# Pixie328.net
KiCad netlist of a schematic drawn in EAGLE
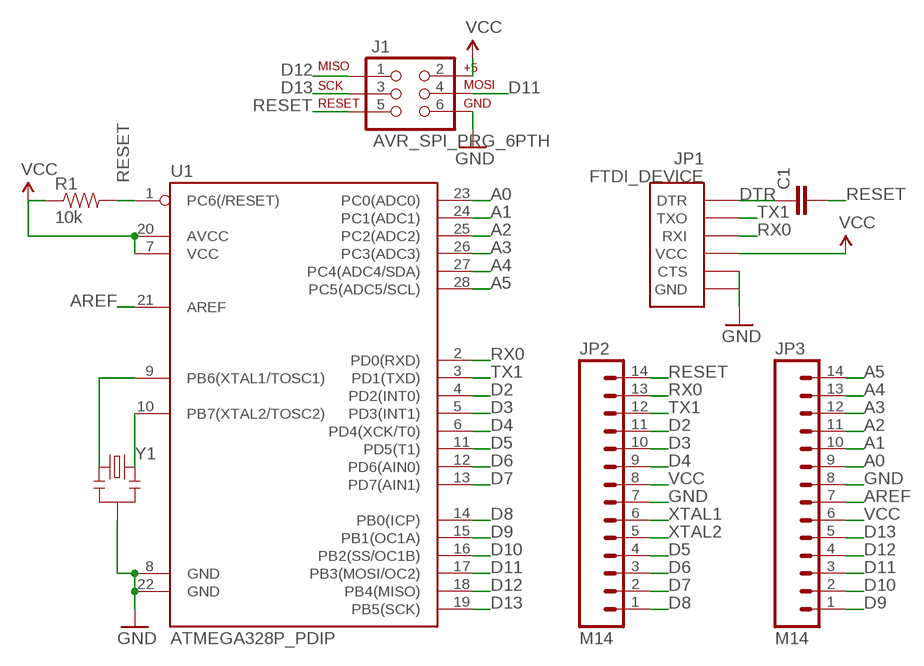
[diagram p0: schematic, sheet 1]

(export (version "E")
  (design (tool "Eeschema 10.0.6"))
  (components
    (comp (ref "C1")
      (value "CAPEZ")
      (footprint "eagle-import:CAP-PTH-SMALLEZ")
      (libsource (lib "eagle-import") (part "CAPEZ"))
    )
    (comp (ref "J1")
      (value "AVR_SPI_PRG_6PTH")
      (footprint "eagle-import:2X3")
      (libsource (lib "eagle-import") (part "AVR_SPI_PRG_6PTH"))
    )
    (comp (ref "JP1")
      (value "FTDI_DEVICE")
      (footprint "eagle-import:FTDI_DEVICE_SIDE")
      (libsource (lib "eagle-import") (part "FTDI_DEVICE"))
    )
    (comp (ref "JP2")
      (value "M14")
      (footprint "eagle-import:1X14")
      (libsource (lib "eagle-import") (part "M14"))
    )
    (comp (ref "JP3")
      (value "M14")
      (footprint "eagle-import:1X14")
      (libsource (lib "eagle-import") (part "M14"))
    )
    (comp (ref "R1")
      (value "10k")
      (footprint "eagle-import:AXIAL-0.3")
      (libsource (lib "eagle-import") (part "RESISTORAXIAL-0.3"))
    )
    (comp (ref "U1")
      (value "ATMEGA328P_PDIP")
      (footprint "eagle-import:DIL28-3")
      (libsource (lib "eagle-import") (part "ATMEGA328P_PDIP"))
    )
    (comp (ref "Y1")
      (value "RESONATORPTH")
      (footprint "eagle-import:RESONATOR-PTH")
      (libsource (lib "eagle-import") (part "RESONATORPTH"))
    )
  )
  (nets
    (net (code "1") (name "/A0") (class "Default")
      (node (ref "JP3") (pin "9") (pinfunction "9_9") (pintype "passive"))
      (node (ref "U1") (pin "23") (pinfunction "PC0(ADC0)_23") (pintype "bidirectional"))
    )
    (net (code "2") (name "/A1") (class "Default")
      (node (ref "JP3") (pin "10") (pinfunction "10_10") (pintype "passive"))
      (node (ref "U1") (pin "24") (pinfunction "PC1(ADC1)_24") (pintype "bidirectional"))
    )
    (net (code "3") (name "/A2") (class "Default")
      (node (ref "JP3") (pin "11") (pinfunction "11_11") (pintype "passive"))
      (node (ref "U1") (pin "25") (pinfunction "PC2(ADC2)_25") (pintype "bidirectional"))
    )
    (net (code "4") (name "/A3") (class "Default")
      (node (ref "JP3") (pin "12") (pinfunction "12_12") (pintype "passive"))
      (node (ref "U1") (pin "26") (pinfunction "PC3(ADC3)_26") (pintype "bidirectional"))
    )
    (net (code "5") (name "/A4") (class "Default")
      (node (ref "JP3") (pin "13") (pinfunction "13_13") (pintype "passive"))
      (node (ref "U1") (pin "27") (pinfunction "PC4(ADC4/SDA)_27") (pintype "bidirectional"))
    )
    (net (code "6") (name "/A5") (class "Default")
      (node (ref "JP3") (pin "14") (pinfunction "14_14") (pintype "passive"))
      (node (ref "U1") (pin "28") (pinfunction "PC5(ADC5/SCL)_28") (pintype "bidirectional"))
    )
    (net (code "7") (name "/AREF") (class "Default")
      (node (ref "JP3") (pin "7") (pinfunction "7_7") (pintype "passive"))
      (node (ref "U1") (pin "21") (pinfunction "AREF_21") (pintype "bidirectional"))
    )
    (net (code "8") (name "/D2") (class "Default")
      (node (ref "JP2") (pin "11") (pinfunction "11_11") (pintype "passive"))
      (node (ref "U1") (pin "4") (pinfunction "PD2(INT0)_4") (pintype "bidirectional"))
    )
    (net (code "9") (name "/D3") (class "Default")
      (node (ref "JP2") (pin "10") (pinfunction "10_10") (pintype "passive"))
      (node (ref "U1") (pin "5") (pinfunction "PD3(INT1)_5") (pintype "bidirectional"))
    )
    (net (code "10") (name "/D4") (class "Default")
      (node (ref "JP2") (pin "9") (pinfunction "9_9") (pintype "passive"))
      (node (ref "U1") (pin "6") (pinfunction "PD4(XCK/T0)_6") (pintype "bidirectional"))
    )
    (net (code "11") (name "/D5") (class "Default")
      (node (ref "JP2") (pin "4") (pinfunction "4_4") (pintype "passive"))
      (node (ref "U1") (pin "11") (pinfunction "PD5(T1)_11") (pintype "bidirectional"))
    )
    (net (code "12") (name "/D6") (class "Default")
      (node (ref "JP2") (pin "3") (pinfunction "3_3") (pintype "passive"))
      (node (ref "U1") (pin "12") (pinfunction "PD6(AIN0)_12") (pintype "bidirectional"))
    )
    (net (code "13") (name "/D7") (class "Default")
      (node (ref "JP2") (pin "2") (pinfunction "2_2") (pintype "passive"))
      (node (ref "U1") (pin "13") (pinfunction "PD7(AIN1)_13") (pintype "bidirectional"))
    )
    (net (code "14") (name "/D8") (class "Default")
      (node (ref "JP2") (pin "1") (pinfunction "1_1") (pintype "passive"))
      (node (ref "U1") (pin "14") (pinfunction "PB0(ICP)_14") (pintype "bidirectional"))
    )
    (net (code "15") (name "/D9") (class "Default")
      (node (ref "JP3") (pin "1") (pinfunction "1_1") (pintype "passive"))
      (node (ref "U1") (pin "15") (pinfunction "PB1(OC1A)_15") (pintype "bidirectional"))
    )
    (net (code "16") (name "/D10") (class "Default")
      (node (ref "JP3") (pin "2") (pinfunction "2_2") (pintype "passive"))
      (node (ref "U1") (pin "16") (pinfunction "PB2(SS/OC1B)_16") (pintype "bidirectional"))
    )
    (net (code "17") (name "/D11") (class "Default")
      (node (ref "J1") (pin "4") (pinfunction "4_4") (pintype "passive"))
      (node (ref "JP3") (pin "3") (pinfunction "3_3") (pintype "passive"))
      (node (ref "U1") (pin "17") (pinfunction "PB3(MOSI/OC2)_17") (pintype "bidirectional"))
    )
    (net (code "18") (name "/D12") (class "Default")
      (node (ref "J1") (pin "1") (pinfunction "1_1") (pintype "passive"))
      (node (ref "JP3") (pin "4") (pinfunction "4_4") (pintype "passive"))
      (node (ref "U1") (pin "18") (pinfunction "PB4(MISO)_18") (pintype "bidirectional"))
    )
    (net (code "19") (name "/D13") (class "Default")
      (node (ref "J1") (pin "3") (pinfunction "3_3") (pintype "passive"))
      (node (ref "JP3") (pin "5") (pinfunction "5_5") (pintype "passive"))
      (node (ref "U1") (pin "19") (pinfunction "PB5(SCK)_19") (pintype "bidirectional"))
    )
    (net (code "20") (name "/DTR") (class "Default")
      (node (ref "C1") (pin "1") (pinfunction "1_1") (pintype "passive"))
      (node (ref "JP1") (pin "P$1") (pinfunction "DTR_P$1") (pintype "bidirectional"))
    )
    (net (code "21") (name "/RESET") (class "Default")
      (node (ref "C1") (pin "2") (pinfunction "2_2") (pintype "passive"))
      (node (ref "J1") (pin "5") (pinfunction "5_5") (pintype "passive"))
      (node (ref "JP2") (pin "14") (pinfunction "14_14") (pintype "passive"))
      (node (ref "R1") (pin "P$2") (pinfunction "2_P$2") (pintype "passive"))
      (node (ref "U1") (pin "1") (pinfunction "PC6(/RESET)_1") (pintype "bidirectional"))
    )
    (net (code "22") (name "/RX0") (class "Default")
      (node (ref "JP1") (pin "P$3") (pinfunction "RXI_P$3") (pintype "bidirectional"))
      (node (ref "JP2") (pin "13") (pinfunction "13_13") (pintype "passive"))
      (node (ref "U1") (pin "2") (pinfunction "PD0(RXD)_2") (pintype "bidirectional"))
    )
    (net (code "23") (name "/TX1") (class "Default")
      (node (ref "JP1") (pin "P$2") (pinfunction "TXO_P$2") (pintype "bidirectional"))
      (node (ref "JP2") (pin "12") (pinfunction "12_12") (pintype "passive"))
      (node (ref "U1") (pin "3") (pinfunction "PD1(TXD)_3") (pintype "bidirectional"))
    )
    (net (code "24") (name "/XTAL1") (class "Default")
      (node (ref "JP2") (pin "6") (pinfunction "6_6") (pintype "passive"))
      (node (ref "U1") (pin "9") (pinfunction "PB6(XTAL1/TOSC1)_9") (pintype "bidirectional"))
      (node (ref "Y1") (pin "1") (pinfunction "1_1") (pintype "passive"))
    )
    (net (code "25") (name "/XTAL2") (class "Default")
      (node (ref "JP2") (pin "5") (pinfunction "5_5") (pintype "passive"))
      (node (ref "U1") (pin "10") (pinfunction "PB7(XTAL2/TOSC2)_10") (pintype "bidirectional"))
      (node (ref "Y1") (pin "3") (pinfunction "3_3") (pintype "passive"))
    )
    (net (code "26") (name "GND") (class "Default")
      (node (ref "J1") (pin "6") (pinfunction "6_6") (pintype "passive"))
      (node (ref "JP1") (pin "P$5") (pinfunction "CTS_P$5") (pintype "bidirectional"))
      (node (ref "JP1") (pin "P$6") (pinfunction "GND_P$6") (pintype "bidirectional"))
      (node (ref "JP2") (pin "7") (pinfunction "7_7") (pintype "passive"))
      (node (ref "JP3") (pin "8") (pinfunction "8_8") (pintype "passive"))
      (node (ref "U1") (pin "22") (pinfunction "GND_22") (pintype "bidirectional"))
      (node (ref "U1") (pin "8") (pinfunction "GND_8") (pintype "bidirectional"))
      (node (ref "Y1") (pin "2") (pinfunction "2_2") (pintype "passive"))
    )
    (net (code "27") (name "VCC") (class "Default")
      (node (ref "J1") (pin "2") (pinfunction "2_2") (pintype "passive"))
      (node (ref "JP1") (pin "P$4") (pinfunction "VCC_P$4") (pintype "bidirectional"))
      (node (ref "JP2") (pin "8") (pinfunction "8_8") (pintype "passive"))
      (node (ref "JP3") (pin "6") (pinfunction "6_6") (pintype "passive"))
      (node (ref "R1") (pin "P$1") (pinfunction "1_P$1") (pintype "passive"))
      (node (ref "U1") (pin "20") (pinfunction "AVCC_20") (pintype "bidirectional"))
      (node (ref "U1") (pin "7") (pinfunction "VCC_7") (pintype "bidirectional"))
    )
  )
)
